# Antlaz-v0_1.net
KiCad netlist of a schematic drawn in EAGLE
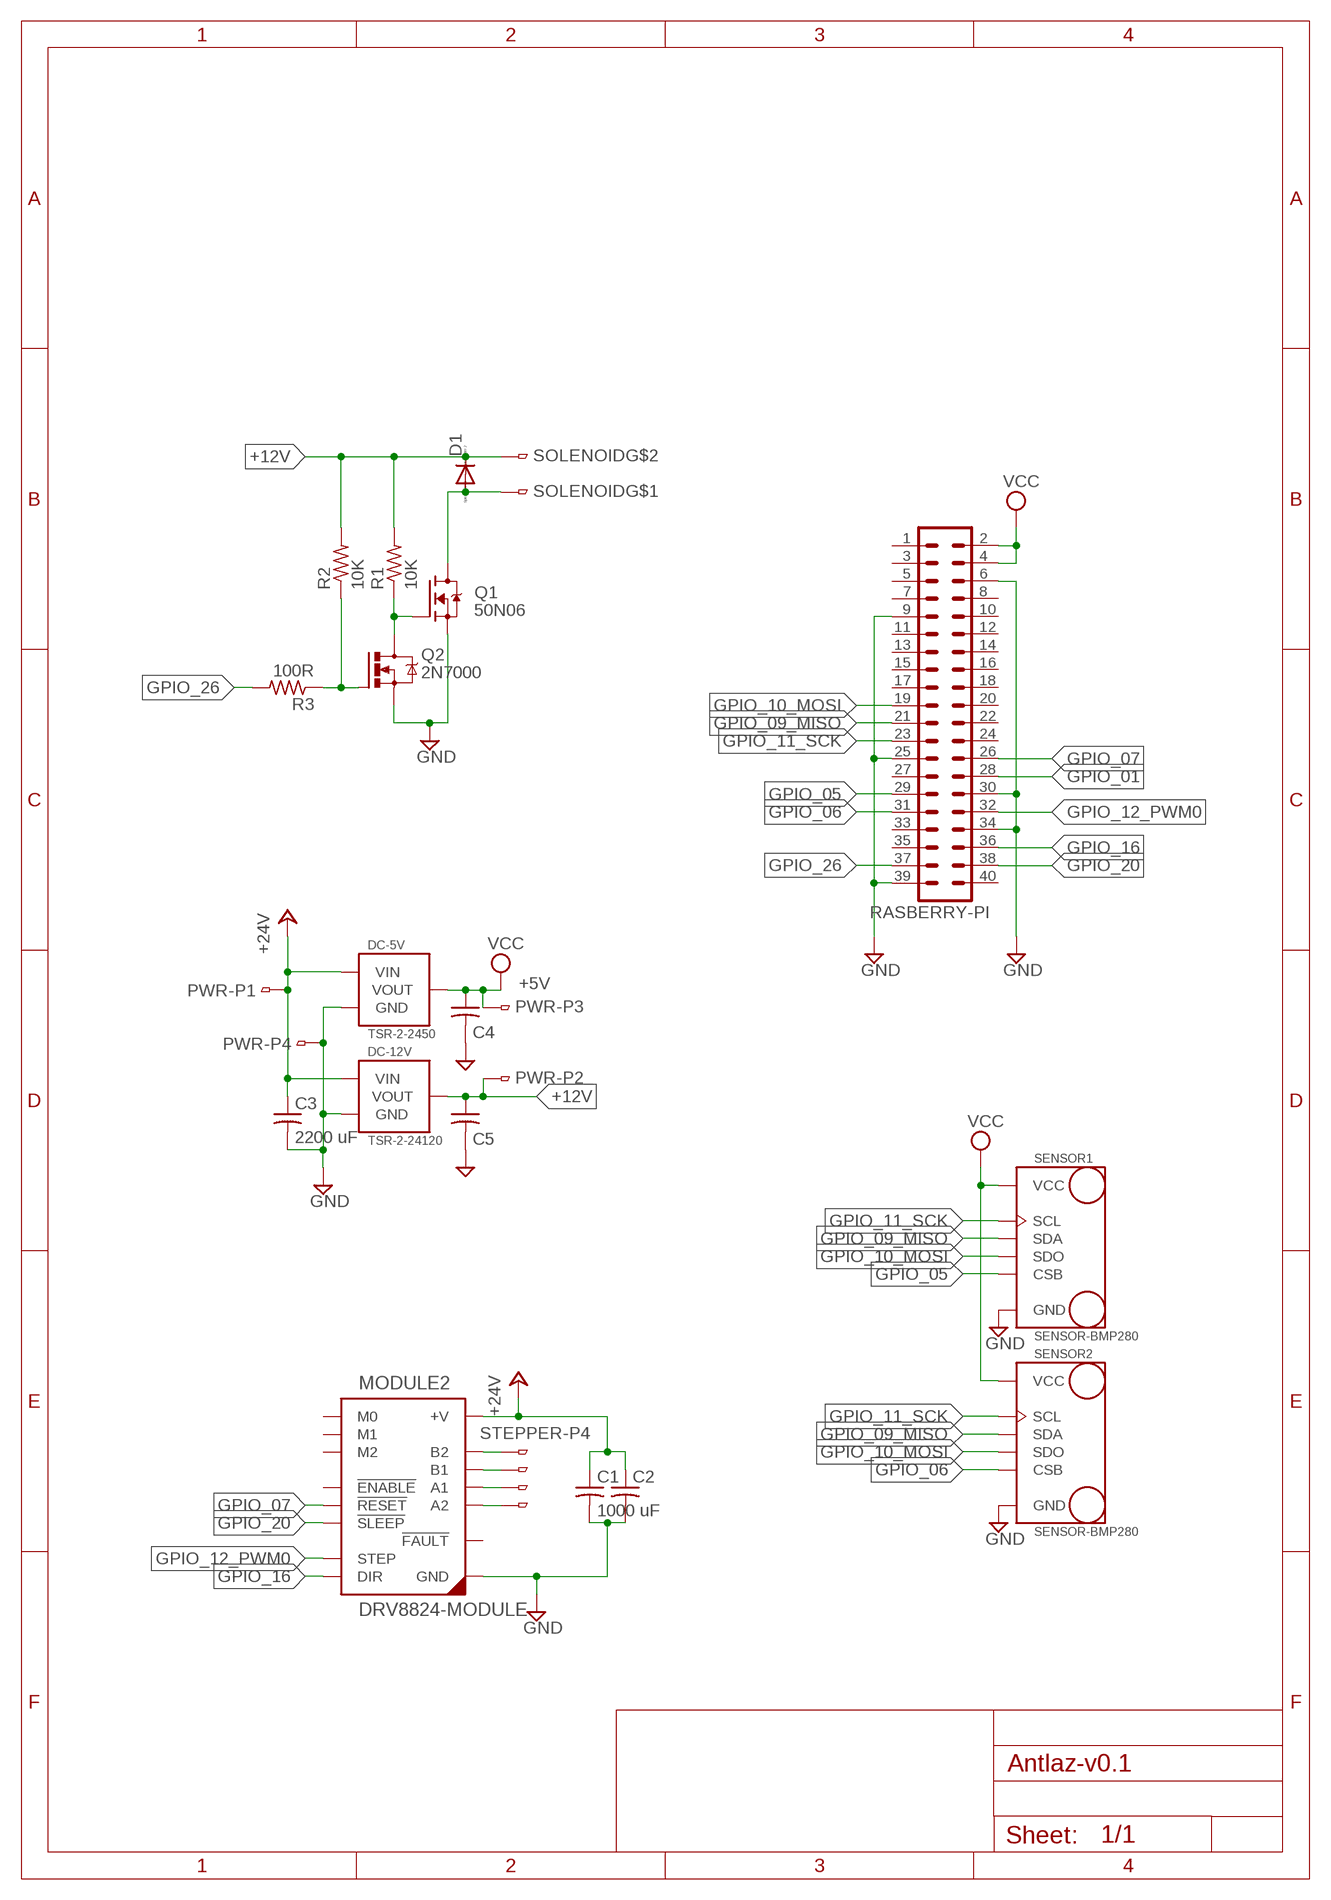
[diagram p0: schematic, sheet 1]

(export (version "E")
  (design (tool "Eeschema 10.0.6"))
  (components
    (comp (ref "C1")
      (value "1000 uF")
      (footprint "eagle-import:CAP_18MM")
      (libsource (lib "eagle-import") (part "C-US_DIA-18MM"))
    )
    (comp (ref "C2")
      (value "C-US_BYPASS")
      (footprint "eagle-import:KEMET-CERMAIC")
      (libsource (lib "eagle-import") (part "C-US_BYPASS"))
    )
    (comp (ref "C3")
      (value "2200 uF")
      (footprint "eagle-import:CAP_18MM")
      (libsource (lib "eagle-import") (part "C-US_DIA-18MM"))
    )
    (comp (ref "C4")
      (value "C-US_BYPASS")
      (footprint "eagle-import:KEMET-CERMAIC")
      (libsource (lib "eagle-import") (part "C-US_BYPASS"))
    )
    (comp (ref "C5")
      (value "C-US_BYPASS")
      (footprint "eagle-import:KEMET-CERMAIC")
      (libsource (lib "eagle-import") (part "C-US_BYPASS"))
    )
    (comp (ref "D1")
      (value "DIODEDO07")
      (footprint "eagle-import:DO07")
      (libsource (lib "eagle-import") (part "DIODEDO07"))
    )
    (comp (ref "DC-5V")
      (value "TSR-2-2450")
      (footprint "eagle-import:DCDC_TSR2")
      (libsource (lib "eagle-import") (part "DC-DC_MODULE-TSR_2"))
    )
    (comp (ref "DC-12V")
      (value "TSR-2-24120")
      (footprint "eagle-import:DCDC_TSR2")
      (libsource (lib "eagle-import") (part "DC-DC_MODULE-TSR_2"))
    )
    (comp (ref "MODULE2")
      (value "DRV8824-MODULE")
      (footprint "eagle-import:DRV8825")
      (libsource (lib "eagle-import") (part "DRV8824-MODULE"))
    )
    (comp (ref "PWR")
      (value "CONN-4")
      (footprint "eagle-import:CONN-PHEONIX-3,5MM-4")
      (libsource (lib "eagle-import") (part "CONN-4"))
    )
    (comp (ref "Q1")
      (value "50N06")
      (footprint "eagle-import:TO220")
      (libsource (lib "eagle-import") (part "NMOSFET_"))
    )
    (comp (ref "Q2")
      (value "2N7000")
      (footprint "eagle-import:TO92")
      (libsource (lib "eagle-import") (part "NMOSFETTO92_"))
    )
    (comp (ref "R1")
      (value "10K")
      (footprint "eagle-import:0207_10")
      (libsource (lib "eagle-import") (part "R-US_0207/10"))
    )
    (comp (ref "R2")
      (value "10K")
      (footprint "eagle-import:0207_10")
      (libsource (lib "eagle-import") (part "R-US_0207/10"))
    )
    (comp (ref "R3")
      (value "100R")
      (footprint "eagle-import:0207_10")
      (libsource (lib "eagle-import") (part "R-US_0207/10"))
    )
    (comp (ref "RASBERRY-PI")
      (value "MA20-2")
      (footprint "eagle-import:MA20-2")
      (libsource (lib "eagle-import") (part "MA20-2"))
    )
    (comp (ref "SENSOR1")
      (value "SENSOR-BMP280")
      (footprint "eagle-import:MA06-1")
      (libsource (lib "eagle-import") (part "SENSOR-BMP280"))
    )
    (comp (ref "SENSOR2")
      (value "SENSOR-BMP280")
      (footprint "eagle-import:MA06-1")
      (libsource (lib "eagle-import") (part "SENSOR-BMP280"))
    )
    (comp (ref "SOLENOID")
      (value "CONN-2")
      (footprint "eagle-import:CONN-PHEONIX-3,5MM-2")
      (libsource (lib "eagle-import") (part "CONN-2"))
    )
    (comp (ref "STEPPER")
      (value "CONN-4")
      (footprint "eagle-import:CONN-PHEONIX-3,5MM-4")
      (libsource (lib "eagle-import") (part "CONN-4"))
    )
  )
  (nets
    (net (code "1") (name "+12V") (class "Default")
      (node (ref "C5") (pin "1") (pinfunction "1_1") (pintype "passive"))
      (node (ref "D1") (pin "C") (pinfunction "C_C") (pintype "passive"))
      (node (ref "DC-12V") (pin "P$3") (pinfunction "VOUT_P$3") (pintype "bidirectional"))
      (node (ref "PWR") (pin "P$2") (pinfunction "1_P$2") (pintype "passive"))
      (node (ref "R1") (pin "2") (pinfunction "2_2") (pintype "passive"))
      (node (ref "R2") (pin "2") (pinfunction "2_2") (pintype "passive"))
      (node (ref "SOLENOID") (pin "P$2") (pinfunction "1_P$2") (pintype "passive"))
    )
    (net (code "2") (name "+24V") (class "Default")
      (node (ref "C1") (pin "1") (pinfunction "1_1") (pintype "passive"))
      (node (ref "C2") (pin "1") (pinfunction "1_1") (pintype "passive"))
      (node (ref "C3") (pin "1") (pinfunction "1_1") (pintype "passive"))
      (node (ref "DC-12V") (pin "P$1") (pinfunction "VIN_P$1") (pintype "bidirectional"))
      (node (ref "DC-5V") (pin "P$1") (pinfunction "VIN_P$1") (pintype "bidirectional"))
      (node (ref "MODULE2") (pin "P$16") (pinfunction "+V_P$16") (pintype "bidirectional"))
      (node (ref "PWR") (pin "P$1") (pinfunction "1_P$1") (pintype "passive"))
    )
    (net (code "3") (name "GND") (class "Default")
      (node (ref "C1") (pin "2") (pinfunction "2_2") (pintype "passive"))
      (node (ref "C2") (pin "2") (pinfunction "2_2") (pintype "passive"))
      (node (ref "C3") (pin "2") (pinfunction "2_2") (pintype "passive"))
      (node (ref "C4") (pin "2") (pinfunction "2_2") (pintype "passive"))
      (node (ref "C5") (pin "2") (pinfunction "2_2") (pintype "passive"))
      (node (ref "DC-12V") (pin "P$2") (pinfunction "GND_P$2") (pintype "bidirectional"))
      (node (ref "DC-5V") (pin "P$2") (pinfunction "GND_P$2") (pintype "bidirectional"))
      (node (ref "MODULE2") (pin "P$15") (pinfunction "GND_P$15") (pintype "bidirectional"))
      (node (ref "MODULE2") (pin "P$9") (pinfunction "GND_P$9") (pintype "bidirectional"))
      (node (ref "PWR") (pin "P$4") (pinfunction "1_P$4") (pintype "passive"))
      (node (ref "Q1") (pin "3") (pinfunction "S_3") (pintype "passive"))
      (node (ref "Q2") (pin "3") (pinfunction "S_3") (pintype "passive"))
      (node (ref "RASBERRY-PI") (pin "25") (pinfunction "25_25") (pintype "passive"))
      (node (ref "RASBERRY-PI") (pin "30") (pinfunction "30_30") (pintype "passive"))
      (node (ref "RASBERRY-PI") (pin "34") (pinfunction "34_34") (pintype "passive"))
      (node (ref "RASBERRY-PI") (pin "39") (pinfunction "39_39") (pintype "passive"))
      (node (ref "RASBERRY-PI") (pin "6") (pinfunction "6_6") (pintype "passive"))
      (node (ref "RASBERRY-PI") (pin "9") (pinfunction "9_9") (pintype "passive"))
      (node (ref "SENSOR1") (pin "2") (pinfunction "GND_2") (pintype "bidirectional"))
      (node (ref "SENSOR2") (pin "2") (pinfunction "GND_2") (pintype "bidirectional"))
    )
    (net (code "4") (name "GPIO_01") (class "Default")
      (node (ref "RASBERRY-PI") (pin "28") (pinfunction "28_28") (pintype "passive"))
    )
    (net (code "5") (name "GPIO_05") (class "Default")
      (node (ref "RASBERRY-PI") (pin "29") (pinfunction "29_29") (pintype "passive"))
      (node (ref "SENSOR1") (pin "5") (pinfunction "CSB_5") (pintype "bidirectional"))
    )
    (net (code "6") (name "GPIO_06") (class "Default")
      (node (ref "RASBERRY-PI") (pin "31") (pinfunction "31_31") (pintype "passive"))
      (node (ref "SENSOR2") (pin "5") (pinfunction "CSB_5") (pintype "bidirectional"))
    )
    (net (code "7") (name "GPIO_07") (class "Default")
      (node (ref "MODULE2") (pin "P$5") (pinfunction "~{RESET}_P$5") (pintype "bidirectional"))
      (node (ref "RASBERRY-PI") (pin "26") (pinfunction "26_26") (pintype "passive"))
    )
    (net (code "8") (name "GPIO_09_MISO") (class "Default")
      (node (ref "RASBERRY-PI") (pin "21") (pinfunction "21_21") (pintype "passive"))
      (node (ref "SENSOR1") (pin "4") (pinfunction "SDA_4") (pintype "bidirectional"))
      (node (ref "SENSOR2") (pin "4") (pinfunction "SDA_4") (pintype "bidirectional"))
    )
    (net (code "9") (name "GPIO_10_MOSI") (class "Default")
      (node (ref "RASBERRY-PI") (pin "19") (pinfunction "19_19") (pintype "passive"))
      (node (ref "SENSOR1") (pin "6") (pinfunction "SDO_6") (pintype "bidirectional"))
      (node (ref "SENSOR2") (pin "6") (pinfunction "SDO_6") (pintype "bidirectional"))
    )
    (net (code "10") (name "GPIO_11_SCK") (class "Default")
      (node (ref "RASBERRY-PI") (pin "23") (pinfunction "23_23") (pintype "passive"))
      (node (ref "SENSOR1") (pin "3") (pinfunction "SCL_3") (pintype "bidirectional"))
      (node (ref "SENSOR2") (pin "3") (pinfunction "SCL_3") (pintype "bidirectional"))
    )
    (net (code "11") (name "GPIO_12_PWM0") (class "Default")
      (node (ref "MODULE2") (pin "P$7") (pinfunction "STEP_P$7") (pintype "bidirectional"))
      (node (ref "RASBERRY-PI") (pin "32") (pinfunction "32_32") (pintype "passive"))
    )
    (net (code "12") (name "GPIO_16") (class "Default")
      (node (ref "MODULE2") (pin "P$8") (pinfunction "DIR_P$8") (pintype "bidirectional"))
      (node (ref "RASBERRY-PI") (pin "36") (pinfunction "36_36") (pintype "passive"))
    )
    (net (code "13") (name "GPIO_20") (class "Default")
      (node (ref "MODULE2") (pin "P$6") (pinfunction "~{SLEEP}_P$6") (pintype "bidirectional"))
      (node (ref "RASBERRY-PI") (pin "38") (pinfunction "38_38") (pintype "passive"))
    )
    (net (code "14") (name "GPIO_26") (class "Default")
      (node (ref "R3") (pin "2") (pinfunction "2_2") (pintype "passive"))
      (node (ref "RASBERRY-PI") (pin "37") (pinfunction "37_37") (pintype "passive"))
    )
    (net (code "15") (name "Net-(MODULE2-A1)") (class "Default")
      (node (ref "MODULE2") (pin "P$12") (pinfunction "A1_P$12") (pintype "bidirectional"))
      (node (ref "STEPPER") (pin "P$2") (pinfunction "1_P$2") (pintype "passive"))
    )
    (net (code "16") (name "Net-(MODULE2-A2)") (class "Default")
      (node (ref "MODULE2") (pin "P$11") (pinfunction "A2_P$11") (pintype "bidirectional"))
      (node (ref "STEPPER") (pin "P$1") (pinfunction "1_P$1") (pintype "passive"))
    )
    (net (code "17") (name "Net-(MODULE2-B1)") (class "Default")
      (node (ref "MODULE2") (pin "P$13") (pinfunction "B1_P$13") (pintype "bidirectional"))
      (node (ref "STEPPER") (pin "P$3") (pinfunction "1_P$3") (pintype "passive"))
    )
    (net (code "18") (name "Net-(MODULE2-B2)") (class "Default")
      (node (ref "MODULE2") (pin "P$14") (pinfunction "B2_P$14") (pintype "bidirectional"))
      (node (ref "STEPPER") (pin "P$4") (pinfunction "1_P$4") (pintype "passive"))
    )
    (net (code "19") (name "Net-(Q1-D)") (class "Default")
      (node (ref "D1") (pin "A") (pinfunction "A_A") (pintype "passive"))
      (node (ref "Q1") (pin "2") (pinfunction "D_2") (pintype "passive"))
      (node (ref "SOLENOID") (pin "P$1") (pinfunction "1_P$1") (pintype "passive"))
    )
    (net (code "20") (name "Net-(Q1-G)") (class "Default")
      (node (ref "Q1") (pin "1") (pinfunction "G_1") (pintype "passive"))
      (node (ref "Q2") (pin "1") (pinfunction "D_1") (pintype "passive"))
      (node (ref "R1") (pin "1") (pinfunction "1_1") (pintype "passive"))
    )
    (net (code "21") (name "Net-(Q2-G)") (class "Default")
      (node (ref "Q2") (pin "2") (pinfunction "G_2") (pintype "passive"))
      (node (ref "R2") (pin "1") (pinfunction "1_1") (pintype "passive"))
      (node (ref "R3") (pin "1") (pinfunction "1_1") (pintype "passive"))
    )
    (net (code "22") (name "VCC") (class "Default")
      (node (ref "C4") (pin "1") (pinfunction "1_1") (pintype "passive"))
      (node (ref "DC-5V") (pin "P$3") (pinfunction "VOUT_P$3") (pintype "bidirectional"))
      (node (ref "PWR") (pin "P$3") (pinfunction "1_P$3") (pintype "passive"))
      (node (ref "RASBERRY-PI") (pin "2") (pinfunction "2_2") (pintype "passive"))
      (node (ref "RASBERRY-PI") (pin "4") (pinfunction "4_4") (pintype "passive"))
      (node (ref "SENSOR1") (pin "1") (pinfunction "VCC_1") (pintype "bidirectional"))
      (node (ref "SENSOR2") (pin "1") (pinfunction "VCC_1") (pintype "bidirectional"))
    )
    (net (code "23") (name "unconnected-(MODULE2-M0-PadP$2)") (class "Default")
      (node (ref "MODULE2") (pin "P$2") (pinfunction "M0_P$2") (pintype "bidirectional"))
    )
    (net (code "24") (name "unconnected-(MODULE2-M1-PadP$3)") (class "Default")
      (node (ref "MODULE2") (pin "P$3") (pinfunction "M1_P$3") (pintype "bidirectional"))
    )
    (net (code "25") (name "unconnected-(MODULE2-M2-PadP$4)") (class "Default")
      (node (ref "MODULE2") (pin "P$4") (pinfunction "M2_P$4") (pintype "bidirectional"))
    )
    (net (code "26") (name "unconnected-(MODULE2-~{ENABLE}-PadP$1)") (class "Default")
      (node (ref "MODULE2") (pin "P$1") (pinfunction "~{ENABLE}_P$1") (pintype "bidirectional"))
    )
    (net (code "27") (name "unconnected-(MODULE2-~{FAULT}-PadP$10)") (class "Default")
      (node (ref "MODULE2") (pin "P$10") (pinfunction "~{FAULT}_P$10") (pintype "bidirectional"))
    )
    (net (code "28") (name "unconnected-(RASBERRY-PI-Pad1)") (class "Default")
      (node (ref "RASBERRY-PI") (pin "1") (pinfunction "1_1") (pintype "passive"))
    )
    (net (code "29") (name "unconnected-(RASBERRY-PI-Pad3)") (class "Default")
      (node (ref "RASBERRY-PI") (pin "3") (pinfunction "3_3") (pintype "passive"))
    )
    (net (code "30") (name "unconnected-(RASBERRY-PI-Pad5)") (class "Default")
      (node (ref "RASBERRY-PI") (pin "5") (pinfunction "5_5") (pintype "passive"))
    )
    (net (code "31") (name "unconnected-(RASBERRY-PI-Pad7)") (class "Default")
      (node (ref "RASBERRY-PI") (pin "7") (pinfunction "7_7") (pintype "passive"))
    )
    (net (code "32") (name "unconnected-(RASBERRY-PI-Pad8)") (class "Default")
      (node (ref "RASBERRY-PI") (pin "8") (pinfunction "8_8") (pintype "passive"))
    )
    (net (code "33") (name "unconnected-(RASBERRY-PI-Pad10)") (class "Default")
      (node (ref "RASBERRY-PI") (pin "10") (pinfunction "10_10") (pintype "passive"))
    )
    (net (code "34") (name "unconnected-(RASBERRY-PI-Pad11)") (class "Default")
      (node (ref "RASBERRY-PI") (pin "11") (pinfunction "11_11") (pintype "passive"))
    )
    (net (code "35") (name "unconnected-(RASBERRY-PI-Pad12)") (class "Default")
      (node (ref "RASBERRY-PI") (pin "12") (pinfunction "12_12") (pintype "passive"))
    )
    (net (code "36") (name "unconnected-(RASBERRY-PI-Pad13)") (class "Default")
      (node (ref "RASBERRY-PI") (pin "13") (pinfunction "13_13") (pintype "passive"))
    )
    (net (code "37") (name "unconnected-(RASBERRY-PI-Pad14)") (class "Default")
      (node (ref "RASBERRY-PI") (pin "14") (pinfunction "14_14") (pintype "passive"))
    )
    (net (code "38") (name "unconnected-(RASBERRY-PI-Pad15)") (class "Default")
      (node (ref "RASBERRY-PI") (pin "15") (pinfunction "15_15") (pintype "passive"))
    )
    (net (code "39") (name "unconnected-(RASBERRY-PI-Pad16)") (class "Default")
      (node (ref "RASBERRY-PI") (pin "16") (pinfunction "16_16") (pintype "passive"))
    )
    (net (code "40") (name "unconnected-(RASBERRY-PI-Pad17)") (class "Default")
      (node (ref "RASBERRY-PI") (pin "17") (pinfunction "17_17") (pintype "passive"))
    )
    (net (code "41") (name "unconnected-(RASBERRY-PI-Pad18)") (class "Default")
      (node (ref "RASBERRY-PI") (pin "18") (pinfunction "18_18") (pintype "passive"))
    )
    (net (code "42") (name "unconnected-(RASBERRY-PI-Pad20)") (class "Default")
      (node (ref "RASBERRY-PI") (pin "20") (pinfunction "20_20") (pintype "passive"))
    )
    (net (code "43") (name "unconnected-(RASBERRY-PI-Pad22)") (class "Default")
      (node (ref "RASBERRY-PI") (pin "22") (pinfunction "22_22") (pintype "passive"))
    )
    (net (code "44") (name "unconnected-(RASBERRY-PI-Pad24)") (class "Default")
      (node (ref "RASBERRY-PI") (pin "24") (pinfunction "24_24") (pintype "passive"))
    )
    (net (code "45") (name "unconnected-(RASBERRY-PI-Pad27)") (class "Default")
      (node (ref "RASBERRY-PI") (pin "27") (pinfunction "27_27") (pintype "passive"))
    )
    (net (code "46") (name "unconnected-(RASBERRY-PI-Pad33)") (class "Default")
      (node (ref "RASBERRY-PI") (pin "33") (pinfunction "33_33") (pintype "passive"))
    )
    (net (code "47") (name "unconnected-(RASBERRY-PI-Pad35)") (class "Default")
      (node (ref "RASBERRY-PI") (pin "35") (pinfunction "35_35") (pintype "passive"))
    )
    (net (code "48") (name "unconnected-(RASBERRY-PI-Pad40)") (class "Default")
      (node (ref "RASBERRY-PI") (pin "40") (pinfunction "40_40") (pintype "passive"))
    )
  )
)
